# LedMatrixMain.net
KiCad netlist of a schematic drawn in Altium Designer
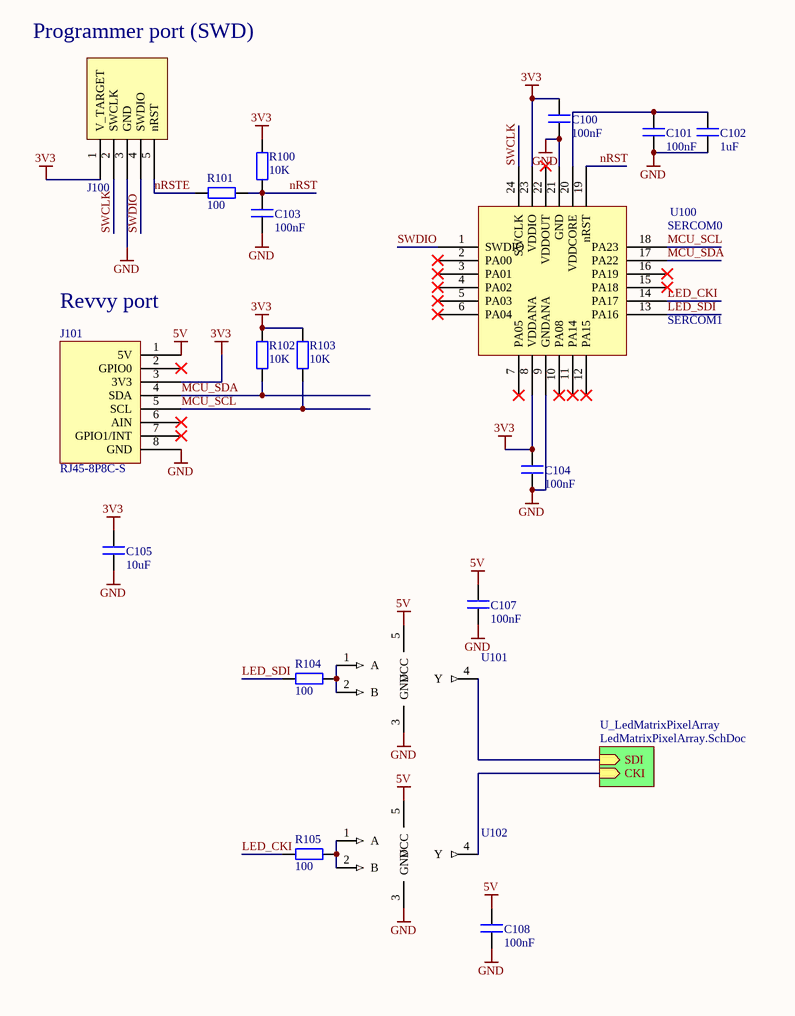
[diagram p0: LedMatrixMain.SchDoc]

(export (version "E")
  (design (tool "Eeschema 10.0.6"))
  (components
    (comp (ref "C100")
      (value "100nF")
      (footprint "CAP1608X06M")
      (libsource (lib "ColorSensor") (part "Capacitor 100n"))
    )
    (comp (ref "C101")
      (value "100nF")
      (footprint "CAP1608X06M")
      (libsource (lib "ColorSensor") (part "Capacitor 100n"))
    )
    (comp (ref "C102")
      (value "1uF")
      (footprint "CAP1608X06M")
      (libsource (lib "ColorSensor") (part "Capacitor 1u"))
    )
    (comp (ref "C103")
      (value "100nF")
      (footprint "CAP1608X06M")
      (libsource (lib "ColorSensor") (part "Capacitor 100n"))
    )
    (comp (ref "C104")
      (value "100nF")
      (footprint "CAP1608X06M")
      (libsource (lib "ColorSensor") (part "Capacitor 100n"))
    )
    (comp (ref "C105")
      (value "10uF")
      (footprint "CAP1608X06M")
      (libsource (lib "ColorSensor") (part "Capacitor 10u"))
    )
    (comp (ref "C107")
      (value "100nF")
      (footprint "CAP1608X06M")
      (libsource (lib "ColorSensor") (part "Capacitor 100n"))
    )
    (comp (ref "C108")
      (value "100nF")
      (footprint "CAP1608X06M")
      (libsource (lib "ColorSensor") (part "Capacitor 100n"))
    )
    (comp (ref "J100")
      (value "SWD")
      (footprint "Sullins_GRPB051VWVN-RC")
      (libsource (lib "ColorSensor") (part "SWD"))
    )
    (comp (ref "J101")
      (value "RJ45-8P8C-S")
      (footprint "RJ45-8P8C")
      (libsource (lib "ColorSensor") (part "RJ45-8P8C-S"))
    )
    (comp (ref "R100")
      (value "10K")
      (footprint "RESC1608X06M")
      (libsource (lib "ColorSensor") (part "Resistor 10K"))
    )
    (comp (ref "R101")
      (value "100")
      (footprint "RESC1608X06M")
      (libsource (lib "ColorSensor") (part "Resistor 100"))
    )
    (comp (ref "R102")
      (value "10K")
      (footprint "RESC1608X06M")
      (libsource (lib "ColorSensor") (part "Resistor 10K"))
    )
    (comp (ref "R103")
      (value "10K")
      (footprint "RESC1608X06M")
      (libsource (lib "ColorSensor") (part "Resistor 10K"))
    )
    (comp (ref "R104")
      (value "100")
      (footprint "RESC1608X06M")
      (libsource (lib "ColorSensor") (part "Resistor 100"))
    )
    (comp (ref "R105")
      (value "100")
      (footprint "RESC1608X06M")
      (libsource (lib "ColorSensor") (part "Resistor 100"))
    )
    (comp (ref "U100")
      (value "ATSAML10D16")
      (footprint "QFN50P400X400X90_HS-25N")
      (description "48MHz 32bit ARM MCU")
      (libsource (lib "ColorSensor") (part "ATSAML10D16"))
    )
    (comp (ref "U101")
      (value "OR gate")
      (footprint "SamacSys:SOT95P270X145-5N")
      (fields (field (name "MANUFACTURER_PART_NUMBER") "SN74LV1T32DCKR"))
      (libsource (lib "ColorSensor") (part "SN74LV1T32"))
    )
    (comp (ref "U102")
      (value "OR gate")
      (footprint "SamacSys:SOT95P270X145-5N")
      (fields (field (name "MANUFACTURER_PART_NUMBER") "SN74LV1T32DCKR"))
      (libsource (lib "ColorSensor") (part "SN74LV1T32"))
    )
  )
  (nets
    (net (code "1") (name "/CKI") (class "Default")
      (node (ref "U102") (pin "4") (pinfunction "Y_4") (pintype "output"))
    )
    (net (code "2") (name "/LED_CKI") (class "Default")
      (node (ref "R105") (pin "1") (pinfunction "1_1") (pintype "passive"))
      (node (ref "U100") (pin "14") (pinfunction "PA17_14") (pintype "passive"))
    )
    (net (code "3") (name "/LED_SDI") (class "Default")
      (node (ref "R104") (pin "1") (pinfunction "1_1") (pintype "passive"))
      (node (ref "U100") (pin "13") (pinfunction "PA16_13") (pintype "passive"))
    )
    (net (code "4") (name "/MCU_SCL") (class "Default")
      (node (ref "J101") (pin "5") (pinfunction "SCL_5") (pintype "passive"))
      (node (ref "R103") (pin "1") (pinfunction "1_1") (pintype "passive"))
      (node (ref "U100") (pin "18") (pinfunction "PA23_18") (pintype "passive"))
    )
    (net (code "5") (name "/MCU_SDA") (class "Default")
      (node (ref "J101") (pin "4") (pinfunction "SDA_4") (pintype "passive"))
      (node (ref "R102") (pin "1") (pinfunction "1_1") (pintype "passive"))
      (node (ref "U100") (pin "17") (pinfunction "PA22_17") (pintype "passive"))
    )
    (net (code "6") (name "/SDI") (class "Default")
      (node (ref "U101") (pin "4") (pinfunction "Y_4") (pintype "output"))
    )
    (net (code "7") (name "/SWCLK") (class "Default")
      (node (ref "J100") (pin "2") (pinfunction "SWCLK_2") (pintype "passive"))
      (node (ref "U100") (pin "24") (pinfunction "SWCLK_24") (pintype "passive"))
    )
    (net (code "8") (name "/SWDIO") (class "Default")
      (node (ref "J100") (pin "4") (pinfunction "SWDIO_4") (pintype "passive"))
      (node (ref "U100") (pin "1") (pinfunction "SWDIO_1") (pintype "passive"))
    )
    (net (code "9") (name "/nRST") (class "Default")
      (node (ref "C103") (pin "2") (pinfunction "2_2") (pintype "passive"))
      (node (ref "R100") (pin "1") (pinfunction "1_1") (pintype "passive"))
      (node (ref "R101") (pin "2") (pinfunction "2_2") (pintype "passive"))
      (node (ref "U100") (pin "19") (pinfunction "nRST_19") (pintype "passive"))
    )
    (net (code "10") (name "/nRSTE") (class "Default")
      (node (ref "J100") (pin "5") (pinfunction "nRST_5") (pintype "passive"))
      (node (ref "R101") (pin "1") (pinfunction "1_1") (pintype "passive"))
    )
    (net (code "11") (name "3V3") (class "Default")
      (node (ref "C100") (pin "2") (pinfunction "2_2") (pintype "passive"))
      (node (ref "C104") (pin "2") (pinfunction "2_2") (pintype "passive"))
      (node (ref "C105") (pin "2") (pinfunction "2_2") (pintype "passive"))
      (node (ref "J100") (pin "1") (pinfunction "V_TARGET_1") (pintype "passive"))
      (node (ref "J101") (pin "3") (pinfunction "3V3_3") (pintype "passive"))
      (node (ref "R100") (pin "2") (pinfunction "2_2") (pintype "passive"))
      (node (ref "R102") (pin "2") (pinfunction "2_2") (pintype "passive"))
      (node (ref "R103") (pin "2") (pinfunction "2_2") (pintype "passive"))
      (node (ref "U100") (pin "23") (pinfunction "VDDIO_23") (pintype "passive"))
      (node (ref "U100") (pin "8") (pinfunction "VDDANA_8") (pintype "passive"))
    )
    (net (code "12") (name "5V") (class "Default")
      (node (ref "C107") (pin "2") (pinfunction "2_2") (pintype "passive"))
      (node (ref "C108") (pin "2") (pinfunction "2_2") (pintype "passive"))
      (node (ref "J101") (pin "1") (pinfunction "5V_1") (pintype "passive"))
      (node (ref "U101") (pin "5") (pinfunction "VCC_5") (pintype "power_in"))
      (node (ref "U102") (pin "5") (pinfunction "VCC_5") (pintype "power_in"))
    )
    (net (code "13") (name "GND") (class "Default")
      (node (ref "C100") (pin "1") (pinfunction "1_1") (pintype "passive"))
      (node (ref "C101") (pin "1") (pinfunction "1_1") (pintype "passive"))
      (node (ref "C102") (pin "1") (pinfunction "1_1") (pintype "passive"))
      (node (ref "C103") (pin "1") (pinfunction "1_1") (pintype "passive"))
      (node (ref "C104") (pin "1") (pinfunction "1_1") (pintype "passive"))
      (node (ref "C105") (pin "1") (pinfunction "1_1") (pintype "passive"))
      (node (ref "C107") (pin "1") (pinfunction "1_1") (pintype "passive"))
      (node (ref "C108") (pin "1") (pinfunction "1_1") (pintype "passive"))
      (node (ref "J100") (pin "3") (pinfunction "GND_3") (pintype "passive"))
      (node (ref "J101") (pin "8") (pinfunction "GND_8") (pintype "passive"))
      (node (ref "U100") (pin "21") (pinfunction "GND_21") (pintype "passive"))
      (node (ref "U100") (pin "9") (pinfunction "GNDANA_9") (pintype "passive"))
      (node (ref "U101") (pin "3") (pinfunction "GND_3") (pintype "power_in"))
      (node (ref "U102") (pin "3") (pinfunction "GND_3") (pintype "power_in"))
    )
    (net (code "14") (name "Net-(U100-VDDCORE)") (class "Default")
      (node (ref "C101") (pin "2") (pinfunction "2_2") (pintype "passive"))
      (node (ref "C102") (pin "2") (pinfunction "2_2") (pintype "passive"))
      (node (ref "U100") (pin "20") (pinfunction "VDDCORE_20") (pintype "passive"))
    )
    (net (code "15") (name "Net-(U101-A)") (class "Default")
      (node (ref "R104") (pin "2") (pinfunction "2_2") (pintype "passive"))
      (node (ref "U101") (pin "1") (pinfunction "A_1") (pintype "input"))
      (node (ref "U101") (pin "2") (pinfunction "B_2") (pintype "input"))
    )
    (net (code "16") (name "Net-(U102-A)") (class "Default")
      (node (ref "R105") (pin "2") (pinfunction "2_2") (pintype "passive"))
      (node (ref "U102") (pin "1") (pinfunction "A_1") (pintype "input"))
      (node (ref "U102") (pin "2") (pinfunction "B_2") (pintype "input"))
    )
    (net (code "17") (name "unconnected-(J101-AIN-Pad6)") (class "Default")
      (node (ref "J101") (pin "6") (pinfunction "AIN_6") (pintype "passive+no_connect"))
    )
    (net (code "18") (name "unconnected-(J101-GPIO0-Pad2)") (class "Default")
      (node (ref "J101") (pin "2") (pinfunction "GPIO0_2") (pintype "passive+no_connect"))
    )
    (net (code "19") (name "unconnected-(J101-GPIO1{slash}INT-Pad7)") (class "Default")
      (node (ref "J101") (pin "7") (pinfunction "GPIO1/INT_7") (pintype "passive+no_connect"))
    )
    (net (code "20") (name "unconnected-(U100-PA00-Pad2)") (class "Default")
      (node (ref "U100") (pin "2") (pinfunction "PA00_2") (pintype "passive+no_connect"))
    )
    (net (code "21") (name "unconnected-(U100-PA01-Pad3)") (class "Default")
      (node (ref "U100") (pin "3") (pinfunction "PA01_3") (pintype "passive+no_connect"))
    )
    (net (code "22") (name "unconnected-(U100-PA02-Pad4)") (class "Default")
      (node (ref "U100") (pin "4") (pinfunction "PA02_4") (pintype "passive+no_connect"))
    )
    (net (code "23") (name "unconnected-(U100-PA03-Pad5)") (class "Default")
      (node (ref "U100") (pin "5") (pinfunction "PA03_5") (pintype "passive+no_connect"))
    )
    (net (code "24") (name "unconnected-(U100-PA04-Pad6)") (class "Default")
      (node (ref "U100") (pin "6") (pinfunction "PA04_6") (pintype "passive+no_connect"))
    )
    (net (code "25") (name "unconnected-(U100-PA05-Pad7)") (class "Default")
      (node (ref "U100") (pin "7") (pinfunction "PA05_7") (pintype "passive+no_connect"))
    )
    (net (code "26") (name "unconnected-(U100-PA08-Pad10)") (class "Default")
      (node (ref "U100") (pin "10") (pinfunction "PA08_10") (pintype "passive+no_connect"))
    )
    (net (code "27") (name "unconnected-(U100-PA14-Pad11)") (class "Default")
      (node (ref "U100") (pin "11") (pinfunction "PA14_11") (pintype "passive+no_connect"))
    )
    (net (code "28") (name "unconnected-(U100-PA15-Pad12)") (class "Default")
      (node (ref "U100") (pin "12") (pinfunction "PA15_12") (pintype "passive+no_connect"))
    )
    (net (code "29") (name "unconnected-(U100-PA18-Pad15)") (class "Default")
      (node (ref "U100") (pin "15") (pinfunction "PA18_15") (pintype "passive+no_connect"))
    )
    (net (code "30") (name "unconnected-(U100-PA19-Pad16)") (class "Default")
      (node (ref "U100") (pin "16") (pinfunction "PA19_16") (pintype "passive+no_connect"))
    )
    (net (code "31") (name "unconnected-(U100-VDDOUT-Pad22)") (class "Default")
      (node (ref "U100") (pin "22") (pinfunction "VDDOUT_22") (pintype "passive+no_connect"))
    )
  )
)
